# R88_R98.net
KiCad netlist of a schematic drawn in Altium Designer
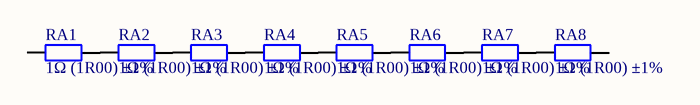
[diagram p0: R88_R98.SchDoc]

(export (version "E")
  (design (tool "Eeschema 10.0.6"))
  (components
    (comp (ref "RA1")
      (value "1Ω (1R00) ±1%")
      (footprint "0805_R")
      (description "贴片电阻")
      (libsource (lib "Miscellaneous Devices LC") (part "0805 1Ω (1R00) 1%"))
    )
    (comp (ref "RA2")
      (value "1Ω (1R00) ±1%")
      (footprint "0805_R")
      (description "贴片电阻")
      (libsource (lib "Miscellaneous Devices LC") (part "0805 1Ω (1R00) 1%"))
    )
    (comp (ref "RA3")
      (value "1Ω (1R00) ±1%")
      (footprint "0805_R")
      (description "贴片电阻")
      (libsource (lib "Miscellaneous Devices LC") (part "0805 1Ω (1R00) 1%"))
    )
    (comp (ref "RA4")
      (value "1Ω (1R00) ±1%")
      (footprint "0805_R")
      (description "贴片电阻")
      (libsource (lib "Miscellaneous Devices LC") (part "0805 1Ω (1R00) 1%"))
    )
    (comp (ref "RA5")
      (value "1Ω (1R00) ±1%")
      (footprint "0805_R")
      (description "贴片电阻")
      (libsource (lib "Miscellaneous Devices LC") (part "0805 1Ω (1R00) 1%"))
    )
    (comp (ref "RA6")
      (value "1Ω (1R00) ±1%")
      (footprint "0805_R")
      (description "贴片电阻")
      (libsource (lib "Miscellaneous Devices LC") (part "0805 1Ω (1R00) 1%"))
    )
    (comp (ref "RA7")
      (value "1Ω (1R00) ±1%")
      (footprint "0805_R")
      (description "贴片电阻")
      (libsource (lib "Miscellaneous Devices LC") (part "0805 1Ω (1R00) 1%"))
    )
    (comp (ref "RA8")
      (value "1Ω (1R00) ±1%")
      (footprint "0805_R")
      (description "贴片电阻")
      (libsource (lib "Miscellaneous Devices LC") (part "0805 1Ω (1R00) 1%"))
    )
  )
  (nets
    (net (code "1") (name "Net-(RA1-Pad2)") (class "Default")
      (node (ref "RA1") (pin "2") (pinfunction "2_2") (pintype "passive"))
      (node (ref "RA2") (pin "1") (pinfunction "1_1") (pintype "passive"))
    )
    (net (code "2") (name "Net-(RA2-Pad2)") (class "Default")
      (node (ref "RA2") (pin "2") (pinfunction "2_2") (pintype "passive"))
      (node (ref "RA3") (pin "1") (pinfunction "1_1") (pintype "passive"))
    )
    (net (code "3") (name "Net-(RA3-Pad2)") (class "Default")
      (node (ref "RA3") (pin "2") (pinfunction "2_2") (pintype "passive"))
      (node (ref "RA4") (pin "1") (pinfunction "1_1") (pintype "passive"))
    )
    (net (code "4") (name "Net-(RA4-Pad2)") (class "Default")
      (node (ref "RA4") (pin "2") (pinfunction "2_2") (pintype "passive"))
      (node (ref "RA5") (pin "1") (pinfunction "1_1") (pintype "passive"))
    )
    (net (code "5") (name "Net-(RA5-Pad2)") (class "Default")
      (node (ref "RA5") (pin "2") (pinfunction "2_2") (pintype "passive"))
      (node (ref "RA6") (pin "1") (pinfunction "1_1") (pintype "passive"))
    )
    (net (code "6") (name "Net-(RA6-Pad2)") (class "Default")
      (node (ref "RA6") (pin "2") (pinfunction "2_2") (pintype "passive"))
      (node (ref "RA7") (pin "1") (pinfunction "1_1") (pintype "passive"))
    )
    (net (code "7") (name "Net-(RA7-Pad2)") (class "Default")
      (node (ref "RA7") (pin "2") (pinfunction "2_2") (pintype "passive"))
      (node (ref "RA8") (pin "1") (pinfunction "1_1") (pintype "passive"))
    )
    (net (code "8") (name "unconnected-(RA1-Pad1)") (class "Default")
      (node (ref "RA1") (pin "1") (pinfunction "1_1") (pintype "passive"))
    )
    (net (code "9") (name "unconnected-(RA8-Pad2)") (class "Default")
      (node (ref "RA8") (pin "2") (pinfunction "2_2") (pintype "passive"))
    )
  )
)
